# core09gnd.net
KiCad netlist of a schematic drawn in EAGLE
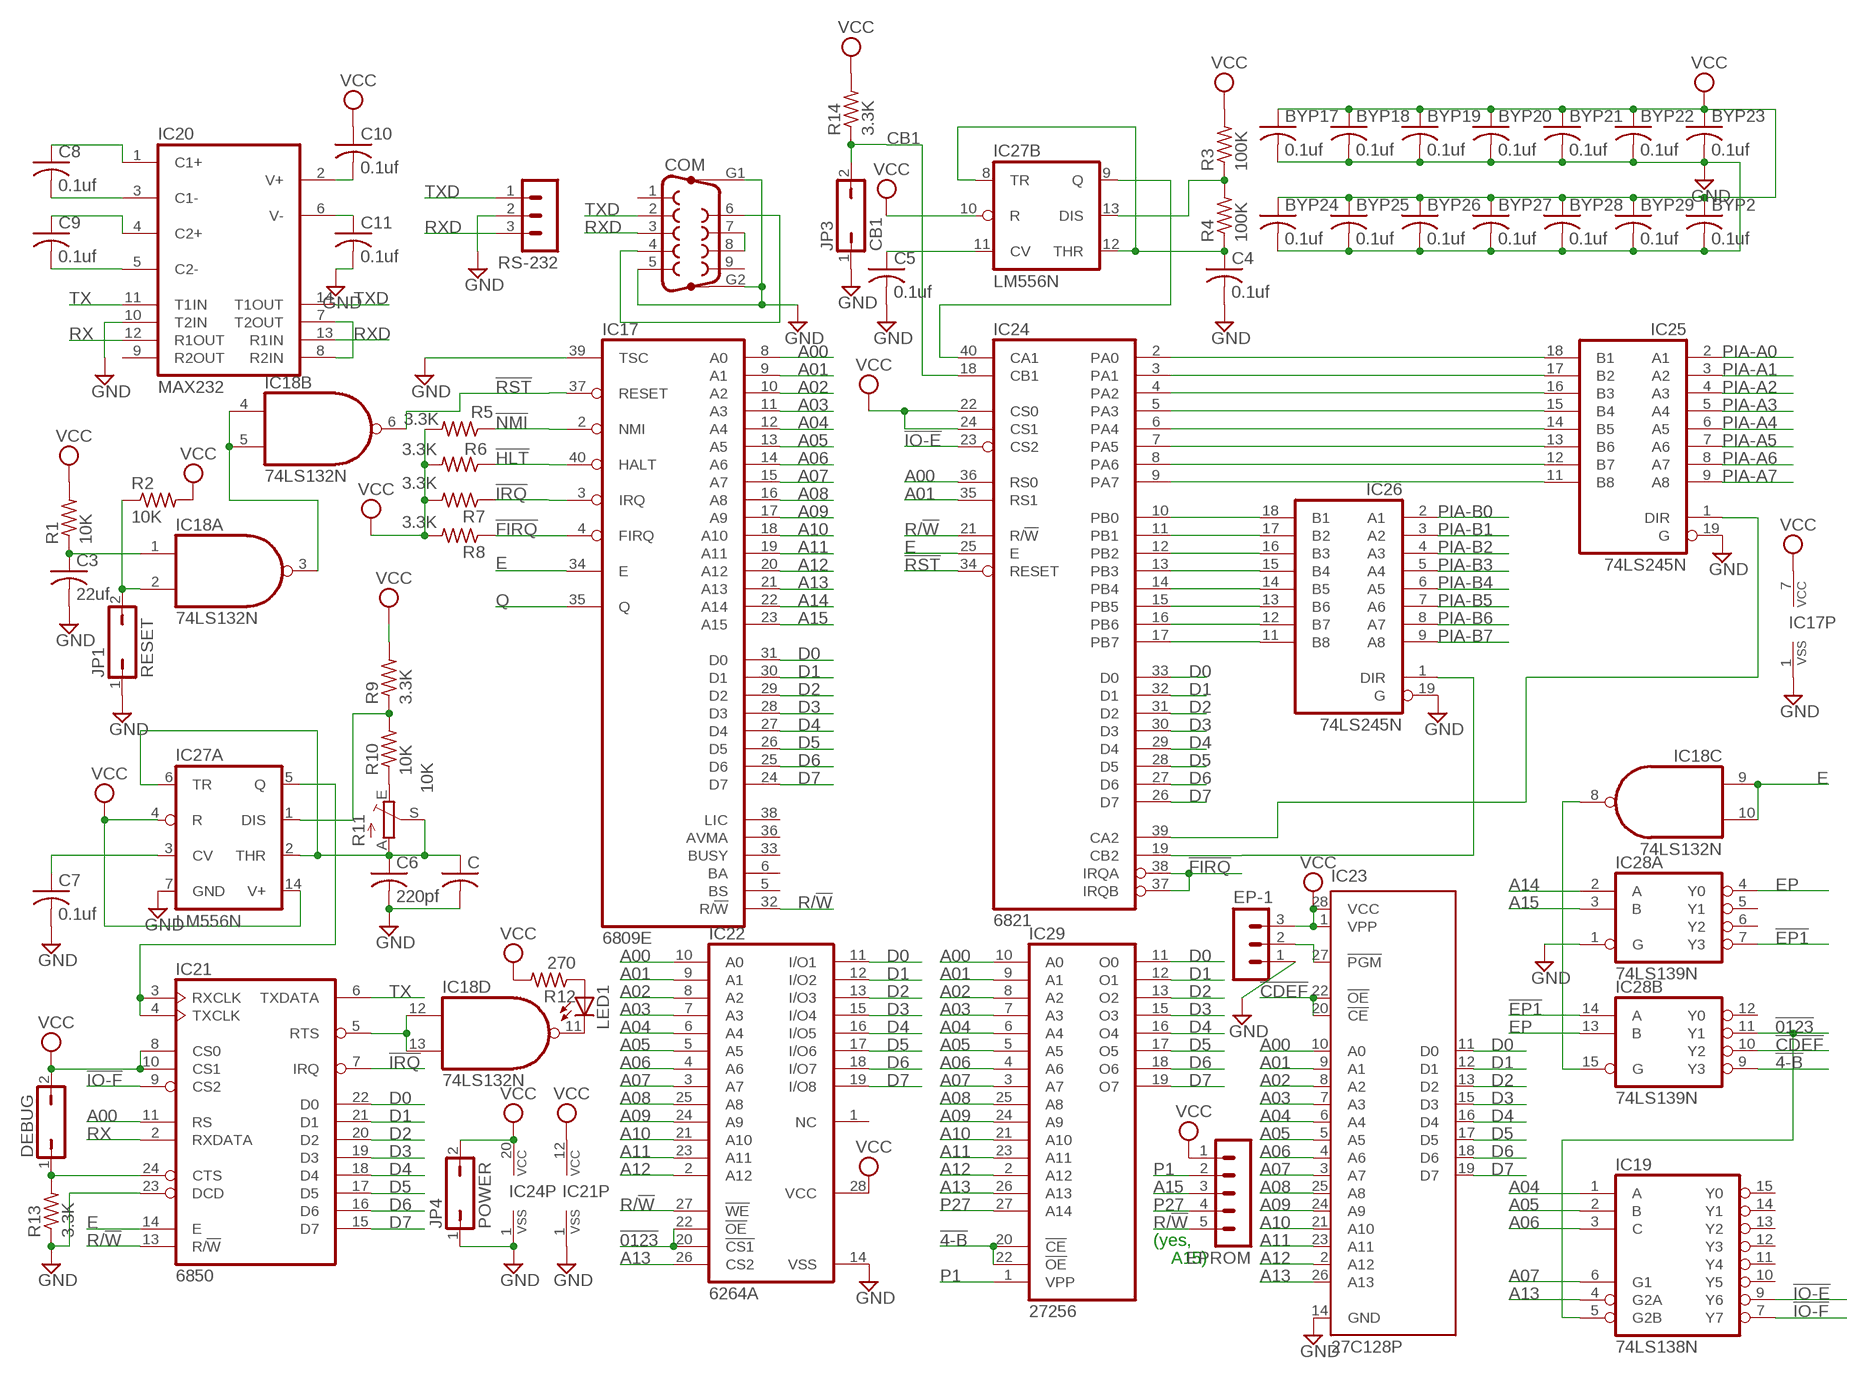
[diagram p0: schematic, sheet 1]
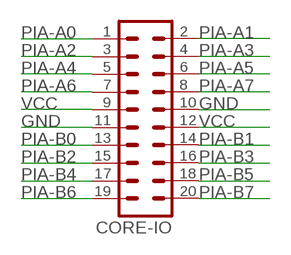
[diagram p1: schematic, sheet 2]
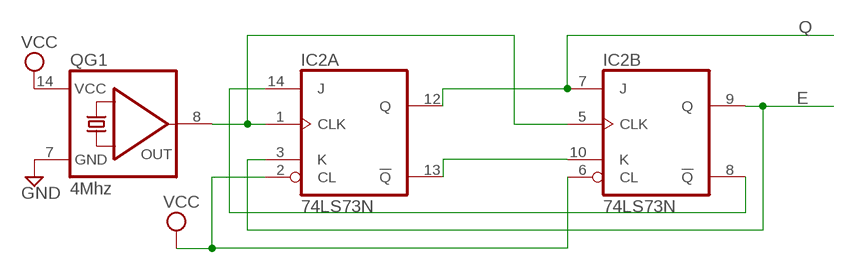
[diagram p2: schematic, sheet 3]

(export (version "E")
  (design (tool "Eeschema 10.0.6"))
  (components
    (comp (ref "IC2")
      (value "74LS73N")
      (footprint "eagle-import:DIL14")
      (libsource (lib "eagle-import") (part "7473NLS"))
    )
    (comp (ref "QG1")
      (value "4Mhz")
      (footprint "eagle-import:DIL14S")
      (libsource (lib "eagle-import") (part "QG5860"))
    )
    (comp (ref "BYP2")
      (value "0.1uf")
      (footprint "eagle-import:C050-025X075")
      (libsource (lib "eagle-import") (part "C-US050-025X075"))
    )
    (comp (ref "BYP17")
      (value "0.1uf")
      (footprint "eagle-import:C050-025X075")
      (libsource (lib "eagle-import") (part "C-US050-025X075"))
    )
    (comp (ref "BYP18")
      (value "0.1uf")
      (footprint "eagle-import:C050-025X075")
      (libsource (lib "eagle-import") (part "C-US050-025X075"))
    )
    (comp (ref "BYP19")
      (value "0.1uf")
      (footprint "eagle-import:C050-025X075")
      (libsource (lib "eagle-import") (part "C-US050-025X075"))
    )
    (comp (ref "BYP20")
      (value "0.1uf")
      (footprint "eagle-import:C050-025X075")
      (libsource (lib "eagle-import") (part "C-US050-025X075"))
    )
    (comp (ref "BYP21")
      (value "0.1uf")
      (footprint "eagle-import:C050-025X075")
      (libsource (lib "eagle-import") (part "C-US050-025X075"))
    )
    (comp (ref "BYP22")
      (value "0.1uf")
      (footprint "eagle-import:C050-025X075")
      (libsource (lib "eagle-import") (part "C-US050-025X075"))
    )
    (comp (ref "BYP23")
      (value "0.1uf")
      (footprint "eagle-import:C050-025X075")
      (libsource (lib "eagle-import") (part "C-US050-025X075"))
    )
    (comp (ref "BYP24")
      (value "0.1uf")
      (footprint "eagle-import:C050-025X075")
      (libsource (lib "eagle-import") (part "C-US050-025X075"))
    )
    (comp (ref "BYP25")
      (value "0.1uf")
      (footprint "eagle-import:C050-025X075")
      (libsource (lib "eagle-import") (part "C-US050-025X075"))
    )
    (comp (ref "BYP26")
      (value "0.1uf")
      (footprint "eagle-import:C050-025X075")
      (libsource (lib "eagle-import") (part "C-US050-025X075"))
    )
    (comp (ref "BYP27")
      (value "0.1uf")
      (footprint "eagle-import:C050-025X075")
      (libsource (lib "eagle-import") (part "C-US050-025X075"))
    )
    (comp (ref "BYP28")
      (value "0.1uf")
      (footprint "eagle-import:C050-025X075")
      (libsource (lib "eagle-import") (part "C-US050-025X075"))
    )
    (comp (ref "BYP29")
      (value "0.1uf")
      (footprint "eagle-import:C050-025X075")
      (libsource (lib "eagle-import") (part "C-US050-025X075"))
    )
    (comp (ref "C")
      (value "C-US050-025X075")
      (footprint "eagle-import:C050-025X075")
      (libsource (lib "eagle-import") (part "C-US050-025X075"))
    )
    (comp (ref "C3")
      (value "22uf")
      (footprint "eagle-import:C102-054X133")
      (libsource (lib "eagle-import") (part "C-US102-054X133"))
    )
    (comp (ref "C4")
      (value "0.1uf")
      (footprint "eagle-import:C050-025X075")
      (libsource (lib "eagle-import") (part "C-US050-025X075"))
    )
    (comp (ref "C5")
      (value "0.1uf")
      (footprint "eagle-import:C050-025X075")
      (libsource (lib "eagle-import") (part "C-US050-025X075"))
    )
    (comp (ref "C6")
      (value "220pf")
      (footprint "eagle-import:C050-025X075")
      (libsource (lib "eagle-import") (part "C-US050-025X075"))
    )
    (comp (ref "C7")
      (value "0.1uf")
      (footprint "eagle-import:C050-025X075")
      (libsource (lib "eagle-import") (part "C-US050-025X075"))
    )
    (comp (ref "C8")
      (value "0.1uf")
      (footprint "eagle-import:C050-025X075")
      (libsource (lib "eagle-import") (part "C-US050-025X075"))
    )
    (comp (ref "C9")
      (value "0.1uf")
      (footprint "eagle-import:C050-025X075")
      (libsource (lib "eagle-import") (part "C-US050-025X075"))
    )
    (comp (ref "C10")
      (value "0.1uf")
      (footprint "eagle-import:C050-025X075")
      (libsource (lib "eagle-import") (part "C-US050-025X075"))
    )
    (comp (ref "C11")
      (value "0.1uf")
      (footprint "eagle-import:C050-025X075")
      (libsource (lib "eagle-import") (part "C-US050-025X075"))
    )
    (comp (ref "COM")
      (value "F09HP")
      (footprint "eagle-import:F09HP")
      (libsource (lib "eagle-import") (part "F09HP"))
    )
    (comp (ref "DEBUG")
      (value "JP1Q")
      (footprint "eagle-import:JP1")
      (libsource (lib "eagle-import") (part "JP1Q"))
    )
    (comp (ref "EP-1")
      (value "MA03-1")
      (footprint "eagle-import:MA03-1")
      (libsource (lib "eagle-import") (part "MA03-1"))
    )
    (comp (ref "EPROM")
      (value "MA05-1")
      (footprint "eagle-import:MA05-1")
      (libsource (lib "eagle-import") (part "MA05-1"))
    )
    (comp (ref "IC17")
      (value "6809E")
      (footprint "eagle-import:DIL40")
      (fields (field (name "MF") "NTE ELECTRONICS") (field (name "MPN") "NTE6809E"))
      (libsource (lib "eagle-import") (part "6809E"))
    )
    (comp (ref "IC18")
      (value "74LS132N")
      (footprint "eagle-import:DIL14")
      (libsource (lib "eagle-import") (part "7400NLS"))
    )
    (comp (ref "IC19")
      (value "74LS138N")
      (footprint "eagle-import:DIL16")
      (libsource (lib "eagle-import") (part "74138NLS"))
    )
    (comp (ref "IC20")
      (value "MAX232")
      (footprint "eagle-import:DIL16")
      (fields (field (name "MF") "MAXIM") (field (name "MPN") "MAX232ACPE+"))
      (libsource (lib "eagle-import") (part "MAX232"))
    )
    (comp (ref "IC21")
      (value "6850")
      (footprint "eagle-import:DIL24")
      (fields (field (name "MF") "NTE ELECTRONICS") (field (name "MPN") "NTE6850"))
      (libsource (lib "eagle-import") (part "6850"))
    )
    (comp (ref "IC22")
      (value "6264A")
      (footprint "eagle-import:DIL28-6")
      (libsource (lib "eagle-import") (part "6264A"))
    )
    (comp (ref "IC23")
      (value "27C128P")
      (footprint "eagle-import:DIL28-6")
      (libsource (lib "eagle-import") (part "27128PC"))
    )
    (comp (ref "IC24")
      (value "6821")
      (footprint "eagle-import:DIL40")
      (fields (field (name "MF") "NTE ELECTRONICS") (field (name "MPN") "NTE6821"))
      (libsource (lib "eagle-import") (part "6821"))
    )
    (comp (ref "IC25")
      (value "74LS245N")
      (footprint "eagle-import:DIL20")
      (libsource (lib "eagle-import") (part "74245NLS"))
    )
    (comp (ref "IC26")
      (value "74LS245N")
      (footprint "eagle-import:DIL20")
      (libsource (lib "eagle-import") (part "74245NLS"))
    )
    (comp (ref "IC27")
      (value "LM556N")
      (footprint "eagle-import:DIL14")
      (libsource (lib "eagle-import") (part "556NLM"))
    )
    (comp (ref "IC28")
      (value "74LS139N")
      (footprint "eagle-import:DIL16")
      (libsource (lib "eagle-import") (part "74139NLS"))
    )
    (comp (ref "IC29")
      (value "27256")
      (footprint "eagle-import:DIL28")
      (libsource (lib "eagle-import") (part "27256"))
    )
    (comp (ref "JP1")
      (value "RESET")
      (footprint "eagle-import:JP1")
      (libsource (lib "eagle-import") (part "JP1Q"))
    )
    (comp (ref "JP3")
      (value "CB1")
      (footprint "eagle-import:JP1")
      (libsource (lib "eagle-import") (part "JP1Q"))
    )
    (comp (ref "JP4")
      (value "POWER")
      (footprint "eagle-import:JP1")
      (libsource (lib "eagle-import") (part "JP1Q"))
    )
    (comp (ref "LED1")
      (value "LED3MM")
      (footprint "eagle-import:LED3MM")
      (libsource (lib "eagle-import") (part "LED3MM"))
    )
    (comp (ref "R1")
      (value "10K")
      (footprint "eagle-import:0207_7")
      (libsource (lib "eagle-import") (part "R-US_0207/7"))
    )
    (comp (ref "R2")
      (value "10K")
      (footprint "eagle-import:0207_7")
      (libsource (lib "eagle-import") (part "R-US_0207/7"))
    )
    (comp (ref "R3")
      (value "100K")
      (footprint "eagle-import:0207_7")
      (libsource (lib "eagle-import") (part "R-US_0207/7"))
    )
    (comp (ref "R4")
      (value "100K")
      (footprint "eagle-import:0207_7")
      (libsource (lib "eagle-import") (part "R-US_0207/7"))
    )
    (comp (ref "R5")
      (value "3.3K")
      (footprint "eagle-import:0207_7")
      (libsource (lib "eagle-import") (part "R-US_0207/7"))
    )
    (comp (ref "R6")
      (value "3.3K")
      (footprint "eagle-import:0207_7")
      (libsource (lib "eagle-import") (part "R-US_0207/7"))
    )
    (comp (ref "R7")
      (value "3.3K")
      (footprint "eagle-import:0207_7")
      (libsource (lib "eagle-import") (part "R-US_0207/7"))
    )
    (comp (ref "R8")
      (value "3.3K")
      (footprint "eagle-import:0207_7")
      (libsource (lib "eagle-import") (part "R-US_0207/7"))
    )
    (comp (ref "R9")
      (value "3.3K")
      (footprint "eagle-import:0207_7")
      (libsource (lib "eagle-import") (part "R-US_0207/7"))
    )
    (comp (ref "R10")
      (value "10K")
      (footprint "eagle-import:0207_7")
      (libsource (lib "eagle-import") (part "R-US_0207/7"))
    )
    (comp (ref "R11")
      (value "10K")
      (footprint "eagle-import:SP19L")
      (libsource (lib "eagle-import") (part "TRIM_EU-B90P"))
    )
    (comp (ref "R12")
      (value "270")
      (footprint "eagle-import:0207_7")
      (libsource (lib "eagle-import") (part "R-US_0207/7"))
    )
    (comp (ref "R13")
      (value "3.3K")
      (footprint "eagle-import:0207_7")
      (libsource (lib "eagle-import") (part "R-US_0207/7"))
    )
    (comp (ref "R14")
      (value "3.3K")
      (footprint "eagle-import:0207_7")
      (libsource (lib "eagle-import") (part "R-US_0207/7"))
    )
    (comp (ref "RS-232")
      (value "MA03-1")
      (footprint "eagle-import:MA03-1")
      (libsource (lib "eagle-import") (part "MA03-1"))
    )
    (comp (ref "CORE-IO")
      (value "MA10-2")
      (footprint "eagle-import:MA10-2")
      (libsource (lib "eagle-import") (part "MA10-2"))
    )
  )
  (nets
    (net (code "1") (name "A00") (class "Default")
      (node (ref "IC17") (pin "8") (pinfunction "A0_8") (pintype "tri_state"))
      (node (ref "IC21") (pin "11") (pinfunction "RS_11") (pintype "input"))
      (node (ref "IC22") (pin "10") (pinfunction "A0_10") (pintype "input"))
      (node (ref "IC23") (pin "10") (pinfunction "A0_10") (pintype "input"))
      (node (ref "IC24") (pin "36") (pinfunction "RS0_36") (pintype "input"))
      (node (ref "IC29") (pin "10") (pinfunction "A0_10") (pintype "input"))
    )
    (net (code "2") (name "A01") (class "Default")
      (node (ref "IC17") (pin "9") (pinfunction "A1_9") (pintype "tri_state"))
      (node (ref "IC22") (pin "9") (pinfunction "A1_9") (pintype "input"))
      (node (ref "IC23") (pin "9") (pinfunction "A1_9") (pintype "input"))
      (node (ref "IC24") (pin "35") (pinfunction "RS1_35") (pintype "input"))
      (node (ref "IC29") (pin "9") (pinfunction "A1_9") (pintype "input"))
    )
    (net (code "3") (name "A02") (class "Default")
      (node (ref "IC17") (pin "10") (pinfunction "A2_10") (pintype "tri_state"))
      (node (ref "IC22") (pin "8") (pinfunction "A2_8") (pintype "input"))
      (node (ref "IC23") (pin "8") (pinfunction "A2_8") (pintype "input"))
      (node (ref "IC29") (pin "8") (pinfunction "A2_8") (pintype "input"))
    )
    (net (code "4") (name "A03") (class "Default")
      (node (ref "IC17") (pin "11") (pinfunction "A3_11") (pintype "tri_state"))
      (node (ref "IC22") (pin "7") (pinfunction "A3_7") (pintype "input"))
      (node (ref "IC23") (pin "7") (pinfunction "A3_7") (pintype "input"))
      (node (ref "IC29") (pin "7") (pinfunction "A3_7") (pintype "input"))
    )
    (net (code "5") (name "A04") (class "Default")
      (node (ref "IC17") (pin "12") (pinfunction "A4_12") (pintype "tri_state"))
      (node (ref "IC19") (pin "1") (pinfunction "A_1") (pintype "input"))
      (node (ref "IC22") (pin "6") (pinfunction "A4_6") (pintype "input"))
      (node (ref "IC23") (pin "6") (pinfunction "A4_6") (pintype "input"))
      (node (ref "IC29") (pin "6") (pinfunction "A4_6") (pintype "input"))
    )
    (net (code "6") (name "A05") (class "Default")
      (node (ref "IC17") (pin "13") (pinfunction "A5_13") (pintype "tri_state"))
      (node (ref "IC19") (pin "2") (pinfunction "B_2") (pintype "input"))
      (node (ref "IC22") (pin "5") (pinfunction "A5_5") (pintype "input"))
      (node (ref "IC23") (pin "5") (pinfunction "A5_5") (pintype "input"))
      (node (ref "IC29") (pin "5") (pinfunction "A5_5") (pintype "input"))
    )
    (net (code "7") (name "A06") (class "Default")
      (node (ref "IC17") (pin "14") (pinfunction "A6_14") (pintype "tri_state"))
      (node (ref "IC19") (pin "3") (pinfunction "C_3") (pintype "input"))
      (node (ref "IC22") (pin "4") (pinfunction "A6_4") (pintype "input"))
      (node (ref "IC23") (pin "4") (pinfunction "A6_4") (pintype "input"))
      (node (ref "IC29") (pin "4") (pinfunction "A6_4") (pintype "input"))
    )
    (net (code "8") (name "A07") (class "Default")
      (node (ref "IC17") (pin "15") (pinfunction "A7_15") (pintype "tri_state"))
      (node (ref "IC19") (pin "6") (pinfunction "G1_6") (pintype "input"))
      (node (ref "IC22") (pin "3") (pinfunction "A7_3") (pintype "input"))
      (node (ref "IC23") (pin "3") (pinfunction "A7_3") (pintype "input"))
      (node (ref "IC29") (pin "3") (pinfunction "A7_3") (pintype "input"))
    )
    (net (code "9") (name "A08") (class "Default")
      (node (ref "IC17") (pin "16") (pinfunction "A8_16") (pintype "tri_state"))
      (node (ref "IC22") (pin "25") (pinfunction "A8_25") (pintype "input"))
      (node (ref "IC23") (pin "25") (pinfunction "A8_25") (pintype "input"))
      (node (ref "IC29") (pin "25") (pinfunction "A8_25") (pintype "input"))
    )
    (net (code "10") (name "A09") (class "Default")
      (node (ref "IC17") (pin "17") (pinfunction "A9_17") (pintype "tri_state"))
      (node (ref "IC22") (pin "24") (pinfunction "A9_24") (pintype "input"))
      (node (ref "IC23") (pin "24") (pinfunction "A9_24") (pintype "input"))
      (node (ref "IC29") (pin "24") (pinfunction "A9_24") (pintype "input"))
    )
    (net (code "11") (name "A10") (class "Default")
      (node (ref "IC17") (pin "18") (pinfunction "A10_18") (pintype "tri_state"))
      (node (ref "IC22") (pin "21") (pinfunction "A10_21") (pintype "input"))
      (node (ref "IC23") (pin "21") (pinfunction "A10_21") (pintype "input"))
      (node (ref "IC29") (pin "21") (pinfunction "A10_21") (pintype "input"))
    )
    (net (code "12") (name "A11") (class "Default")
      (node (ref "IC17") (pin "19") (pinfunction "A11_19") (pintype "tri_state"))
      (node (ref "IC22") (pin "23") (pinfunction "A11_23") (pintype "input"))
      (node (ref "IC23") (pin "23") (pinfunction "A11_23") (pintype "input"))
      (node (ref "IC29") (pin "23") (pinfunction "A11_23") (pintype "input"))
    )
    (net (code "13") (name "A12") (class "Default")
      (node (ref "IC17") (pin "20") (pinfunction "A12_20") (pintype "tri_state"))
      (node (ref "IC22") (pin "2") (pinfunction "A12_2") (pintype "input"))
      (node (ref "IC23") (pin "2") (pinfunction "A12_2") (pintype "input"))
      (node (ref "IC29") (pin "2") (pinfunction "A12_2") (pintype "input"))
    )
    (net (code "14") (name "A13") (class "Default")
      (node (ref "IC17") (pin "21") (pinfunction "A13_21") (pintype "tri_state"))
      (node (ref "IC19") (pin "4") (pinfunction "G2A_4") (pintype "input"))
      (node (ref "IC22") (pin "26") (pinfunction "CS2_26") (pintype "input"))
      (node (ref "IC23") (pin "26") (pinfunction "A13_26") (pintype "input"))
      (node (ref "IC29") (pin "26") (pinfunction "A13_26") (pintype "input"))
    )
    (net (code "15") (name "A14") (class "Default")
      (node (ref "IC17") (pin "22") (pinfunction "A14_22") (pintype "tri_state"))
      (node (ref "IC28") (pin "2") (pinfunction "A_2") (pintype "input"))
    )
    (net (code "16") (name "A15") (class "Default")
      (node (ref "EPROM") (pin "3") (pinfunction "3_3") (pintype "passive"))
      (node (ref "IC17") (pin "23") (pinfunction "A15_23") (pintype "tri_state"))
      (node (ref "IC28") (pin "3") (pinfunction "B_3") (pintype "input"))
    )
    (net (code "17") (name "CB1") (class "Default")
      (node (ref "IC24") (pin "18") (pinfunction "CB1_18") (pintype "input"))
      (node (ref "JP3") (pin "2") (pinfunction "2_2") (pintype "passive"))
      (node (ref "R14") (pin "1") (pinfunction "1_1") (pintype "passive"))
    )
    (net (code "18") (name "D0") (class "Default")
      (node (ref "IC17") (pin "31") (pinfunction "D0_31") (pintype "bidirectional"))
      (node (ref "IC21") (pin "22") (pinfunction "D0_22") (pintype "bidirectional"))
      (node (ref "IC22") (pin "11") (pinfunction "I/O1_11") (pintype "bidirectional"))
      (node (ref "IC23") (pin "11") (pinfunction "D0_11") (pintype "tri_state"))
      (node (ref "IC24") (pin "33") (pinfunction "D0_33") (pintype "bidirectional"))
      (node (ref "IC29") (pin "11") (pinfunction "O0_11") (pintype "tri_state"))
    )
    (net (code "19") (name "D1") (class "Default")
      (node (ref "IC17") (pin "30") (pinfunction "D1_30") (pintype "bidirectional"))
      (node (ref "IC21") (pin "21") (pinfunction "D1_21") (pintype "bidirectional"))
      (node (ref "IC22") (pin "12") (pinfunction "I/O2_12") (pintype "bidirectional"))
      (node (ref "IC23") (pin "12") (pinfunction "D1_12") (pintype "tri_state"))
      (node (ref "IC24") (pin "32") (pinfunction "D1_32") (pintype "bidirectional"))
      (node (ref "IC29") (pin "12") (pinfunction "O1_12") (pintype "tri_state"))
    )
    (net (code "20") (name "D2") (class "Default")
      (node (ref "IC17") (pin "29") (pinfunction "D2_29") (pintype "bidirectional"))
      (node (ref "IC21") (pin "20") (pinfunction "D2_20") (pintype "bidirectional"))
      (node (ref "IC22") (pin "13") (pinfunction "I/O3_13") (pintype "bidirectional"))
      (node (ref "IC23") (pin "13") (pinfunction "D2_13") (pintype "tri_state"))
      (node (ref "IC24") (pin "31") (pinfunction "D2_31") (pintype "bidirectional"))
      (node (ref "IC29") (pin "13") (pinfunction "O2_13") (pintype "tri_state"))
    )
    (net (code "21") (name "D3") (class "Default")
      (node (ref "IC17") (pin "28") (pinfunction "D3_28") (pintype "bidirectional"))
      (node (ref "IC21") (pin "19") (pinfunction "D3_19") (pintype "bidirectional"))
      (node (ref "IC22") (pin "15") (pinfunction "I/O4_15") (pintype "bidirectional"))
      (node (ref "IC23") (pin "15") (pinfunction "D3_15") (pintype "tri_state"))
      (node (ref "IC24") (pin "30") (pinfunction "D3_30") (pintype "bidirectional"))
      (node (ref "IC29") (pin "15") (pinfunction "O3_15") (pintype "tri_state"))
    )
    (net (code "22") (name "D4") (class "Default")
      (node (ref "IC17") (pin "27") (pinfunction "D4_27") (pintype "bidirectional"))
      (node (ref "IC21") (pin "18") (pinfunction "D4_18") (pintype "bidirectional"))
      (node (ref "IC22") (pin "16") (pinfunction "I/O5_16") (pintype "bidirectional"))
      (node (ref "IC23") (pin "16") (pinfunction "D4_16") (pintype "tri_state"))
      (node (ref "IC24") (pin "29") (pinfunction "D4_29") (pintype "bidirectional"))
      (node (ref "IC29") (pin "16") (pinfunction "O4_16") (pintype "tri_state"))
    )
    (net (code "23") (name "D5") (class "Default")
      (node (ref "IC17") (pin "26") (pinfunction "D5_26") (pintype "bidirectional"))
      (node (ref "IC21") (pin "17") (pinfunction "D5_17") (pintype "bidirectional"))
      (node (ref "IC22") (pin "17") (pinfunction "I/O6_17") (pintype "bidirectional"))
      (node (ref "IC23") (pin "17") (pinfunction "D5_17") (pintype "tri_state"))
      (node (ref "IC24") (pin "28") (pinfunction "D5_28") (pintype "bidirectional"))
      (node (ref "IC29") (pin "17") (pinfunction "O5_17") (pintype "tri_state"))
    )
    (net (code "24") (name "D6") (class "Default")
      (node (ref "IC17") (pin "25") (pinfunction "D6_25") (pintype "bidirectional"))
      (node (ref "IC21") (pin "16") (pinfunction "D6_16") (pintype "bidirectional"))
      (node (ref "IC22") (pin "18") (pinfunction "I/O7_18") (pintype "bidirectional"))
      (node (ref "IC23") (pin "18") (pinfunction "D6_18") (pintype "tri_state"))
      (node (ref "IC24") (pin "27") (pinfunction "D6_27") (pintype "bidirectional"))
      (node (ref "IC29") (pin "18") (pinfunction "O6_18") (pintype "tri_state"))
    )
    (net (code "25") (name "D7") (class "Default")
      (node (ref "IC17") (pin "24") (pinfunction "D7_24") (pintype "bidirectional"))
      (node (ref "IC21") (pin "15") (pinfunction "D7_15") (pintype "bidirectional"))
      (node (ref "IC22") (pin "19") (pinfunction "I/O8_19") (pintype "bidirectional"))
      (node (ref "IC23") (pin "19") (pinfunction "D7_19") (pintype "tri_state"))
      (node (ref "IC24") (pin "26") (pinfunction "D7_26") (pintype "bidirectional"))
      (node (ref "IC29") (pin "19") (pinfunction "O7_19") (pintype "tri_state"))
    )
    (net (code "26") (name "E") (class "Default")
      (node (ref "IC17") (pin "34") (pinfunction "E_34") (pintype "input"))
      (node (ref "IC18") (pin "10") (pinfunction "I1_10") (pintype "input"))
      (node (ref "IC18") (pin "9") (pinfunction "I0_9") (pintype "input"))
      (node (ref "IC2") (pin "3") (pinfunction "K_3") (pintype "input"))
      (node (ref "IC2") (pin "9") (pinfunction "Q_9") (pintype "output"))
      (node (ref "IC21") (pin "14") (pinfunction "E_14") (pintype "input"))
      (node (ref "IC24") (pin "25") (pinfunction "E_25") (pintype "input"))
    )
    (net (code "27") (name "EP") (class "Default")
      (node (ref "IC28") (pin "13") (pinfunction "B_13") (pintype "input"))
      (node (ref "IC28") (pin "4") (pinfunction "Y0_4") (pintype "output"))
    )
    (net (code "28") (name "GND") (class "Default")
      (node (ref "BYP17") (pin "2") (pinfunction "2_2") (pintype "passive"))
      (node (ref "BYP18") (pin "2") (pinfunction "2_2") (pintype "passive"))
      (node (ref "BYP19") (pin "2") (pinfunction "2_2") (pintype "passive"))
      (node (ref "BYP2") (pin "2") (pinfunction "2_2") (pintype "passive"))
      (node (ref "BYP20") (pin "2") (pinfunction "2_2") (pintype "passive"))
      (node (ref "BYP21") (pin "2") (pinfunction "2_2") (pintype "passive"))
      (node (ref "BYP22") (pin "2") (pinfunction "2_2") (pintype "passive"))
      (node (ref "BYP23") (pin "2") (pinfunction "2_2") (pintype "passive"))
      (node (ref "BYP24") (pin "2") (pinfunction "2_2") (pintype "passive"))
      (node (ref "BYP25") (pin "2") (pinfunction "2_2") (pintype "passive"))
      (node (ref "BYP26") (pin "2") (pinfunction "2_2") (pintype "passive"))
      (node (ref "BYP27") (pin "2") (pinfunction "2_2") (pintype "passive"))
      (node (ref "BYP28") (pin "2") (pinfunction "2_2") (pintype "passive"))
      (node (ref "BYP29") (pin "2") (pinfunction "2_2") (pintype "passive"))
      (node (ref "C") (pin "2") (pinfunction "2_2") (pintype "passive"))
      (node (ref "C11") (pin "2") (pinfunction "2_2") (pintype "passive"))
      (node (ref "C3") (pin "2") (pinfunction "2_2") (pintype "passive"))
      (node (ref "C4") (pin "2") (pinfunction "2_2") (pintype "passive"))
      (node (ref "C5") (pin "2") (pinfunction "2_2") (pintype "passive"))
      (node (ref "C6") (pin "2") (pinfunction "2_2") (pintype "passive"))
      (node (ref "C7") (pin "2") (pinfunction "2_2") (pintype "passive"))
      (node (ref "COM") (pin "5") (pinfunction "5_5") (pintype "passive"))
      (node (ref "COM") (pin "G1") (pinfunction "G1_G1") (pintype "passive"))
      (node (ref "COM") (pin "G2") (pinfunction "G2_G2") (pintype "passive"))
      (node (ref "CORE-IO") (pin "10") (pinfunction "10_10") (pintype "passive"))
      (node (ref "CORE-IO") (pin "11") (pinfunction "11_11") (pintype "passive"))
      (node (ref "EP-1") (pin "1") (pinfunction "1_1") (pintype "passive"))
      (node (ref "IC17") (pin "1") (pinfunction "VSS_1") (pintype "power_in"))
      (node (ref "IC17") (pin "39") (pinfunction "TSC_39") (pintype "input"))
      (node (ref "IC20") (pin "10") (pinfunction "T2IN_10") (pintype "input"))
      (node (ref "IC21") (pin "1") (pinfunction "VSS_1") (pintype "power_in"))
      (node (ref "IC21") (pin "23") (pinfunction "DCD_23") (pintype "input"))
      (node (ref "IC22") (pin "14") (pinfunction "VSS_14") (pintype "power_in"))
      (node (ref "IC23") (pin "14") (pinfunction "GND_14") (pintype "power_in"))
      (node (ref "IC24") (pin "1") (pinfunction "VSS_1") (pintype "power_in"))
      (node (ref "IC25") (pin "19") (pinfunction "G_19") (pintype "input"))
      (node (ref "IC26") (pin "19") (pinfunction "G_19") (pintype "input"))
      (node (ref "IC27") (pin "7") (pinfunction "GND_7") (pintype "power_in"))
      (node (ref "IC28") (pin "1") (pinfunction "G_1") (pintype "input"))
      (node (ref "JP1") (pin "1") (pinfunction "1_1") (pintype "passive"))
      (node (ref "JP3") (pin "1") (pinfunction "1_1") (pintype "passive"))
      (node (ref "JP4") (pin "1") (pinfunction "1_1") (pintype "passive"))
      (node (ref "QG1") (pin "7") (pinfunction "GND_7") (pintype "power_in"))
      (node (ref "R13") (pin "1") (pinfunction "1_1") (pintype "passive"))
      (node (ref "RS-232") (pin "2") (pinfunction "2_2") (pintype "passive"))
    )
    (net (code "29") (name "Net-(COM-Pad4)") (class "Default")
      (node (ref "COM") (pin "4") (pinfunction "4_4") (pintype "passive"))
      (node (ref "COM") (pin "6") (pinfunction "6_6") (pintype "passive"))
    )
    (net (code "30") (name "Net-(COM-Pad7)") (class "Default")
      (node (ref "COM") (pin "7") (pinfunction "7_7") (pintype "passive"))
      (node (ref "COM") (pin "8") (pinfunction "8_8") (pintype "passive"))
    )
    (net (code "31") (name "Net-(IC2A-CLK)") (class "Default")
      (node (ref "IC2") (pin "1") (pinfunction "CLK_1") (pintype "input"))
      (node (ref "IC2") (pin "5") (pinfunction "CLK_5") (pintype "input"))
      (node (ref "QG1") (pin "8") (pinfunction "OUT_8") (pintype "output"))
    )
    (net (code "32") (name "Net-(IC2A-J)") (class "Default")
      (node (ref "IC2") (pin "14") (pinfunction "J_14") (pintype "input"))
      (node (ref "IC2") (pin "8") (pinfunction "~{Q}_8") (pintype "output"))
    )
    (net (code "33") (name "Net-(IC2A-~{Q})") (class "Default")
      (node (ref "IC2") (pin "10") (pinfunction "K_10") (pintype "input"))
      (node (ref "IC2") (pin "13") (pinfunction "~{Q}_13") (pintype "output"))
    )
    (net (code "34") (name "Net-(IC18A-I0)") (class "Default")
      (node (ref "C3") (pin "1") (pinfunction "1_1") (pintype "passive"))
      (node (ref "IC18") (pin "1") (pinfunction "I0_1") (pintype "input"))
      (node (ref "R1") (pin "1") (pinfunction "1_1") (pintype "passive"))
    )
    (net (code "35") (name "Net-(IC18A-I1)") (class "Default")
      (node (ref "IC18") (pin "2") (pinfunction "I1_2") (pintype "input"))
      (node (ref "JP1") (pin "2") (pinfunction "2_2") (pintype "passive"))
      (node (ref "R2") (pin "1") (pinfunction "1_1") (pintype "passive"))
    )
    (net (code "36") (name "Net-(IC18A-O)") (class "Default")
      (node (ref "IC18") (pin "3") (pinfunction "O_3") (pintype "output"))
      (node (ref "IC18") (pin "4") (pinfunction "I0_4") (pintype "input"))
      (node (ref "IC18") (pin "5") (pinfunction "I1_5") (pintype "input"))
    )
    (net (code "37") (name "Net-(IC18C-O)") (class "Default")
      (node (ref "IC18") (pin "8") (pinfunction "O_8") (pintype "output"))
      (node (ref "IC28") (pin "15") (pinfunction "G_15") (pintype "input"))
    )
    (net (code "38") (name "Net-(IC18D-I0)") (class "Default")
      (node (ref "IC18") (pin "12") (pinfunction "I0_12") (pintype "input"))
      (node (ref "IC18") (pin "13") (pinfunction "I1_13") (pintype "input"))
      (node (ref "IC21") (pin "5") (pinfunction "RTS_5") (pintype "output"))
    )
    (net (code "39") (name "Net-(IC18D-O)") (class "Default")
      (node (ref "IC18") (pin "11") (pinfunction "O_11") (pintype "output"))
      (node (ref "LED1") (pin "K") (pinfunction "C_K") (pintype "passive"))
    )
    (net (code "40") (name "Net-(IC20A-C1+)") (class "Default")
      (node (ref "C8") (pin "1") (pinfunction "1_1") (pintype "passive"))
      (node (ref "IC20") (pin "1") (pinfunction "C1+_1") (pintype "bidirectional"))
    )
    (net (code "41") (name "Net-(IC20A-C1-)") (class "Default")
      (node (ref "C8") (pin "2") (pinfunction "2_2") (pintype "passive"))
      (node (ref "IC20") (pin "3") (pinfunction "C1-_3") (pintype "bidirectional"))
    )
    (net (code "42") (name "Net-(IC20A-C2+)") (class "Default")
      (node (ref "C9") (pin "1") (pinfunction "1_1") (pintype "passive"))
      (node (ref "IC20") (pin "4") (pinfunction "C2+_4") (pintype "bidirectional"))
    )
    (net (code "43") (name "Net-(IC20A-C2-)") (class "Default")
      (node (ref "C9") (pin "2") (pinfunction "2_2") (pintype "passive"))
      (node (ref "IC20") (pin "5") (pinfunction "C2-_5") (pintype "bidirectional"))
    )
    (net (code "44") (name "Net-(IC20A-R2IN)") (class "Default")
      (node (ref "IC20") (pin "7") (pinfunction "T2OUT_7") (pintype "output"))
      (node (ref "IC20") (pin "8") (pinfunction "R2IN_8") (pintype "input"))
    )
    (net (code "45") (name "Net-(IC20A-V+)") (class "Default")
      (node (ref "C10") (pin "2") (pinfunction "2_2") (pintype "passive"))
      (node (ref "IC20") (pin "2") (pinfunction "V+_2") (pintype "bidirectional"))
    )
    (net (code "46") (name "Net-(IC20A-V-)") (class "Default")
      (node (ref "C11") (pin "1") (pinfunction "1_1") (pintype "passive"))
      (node (ref "IC20") (pin "6") (pinfunction "V-_6") (pintype "bidirectional"))
    )
    (net (code "47") (name "Net-(IC21A-CTS)") (class "Default")
      (node (ref "DEBUG") (pin "1") (pinfunction "1_1") (pintype "passive"))
      (node (ref "IC21") (pin "24") (pinfunction "CTS_24") (pintype "input"))
      (node (ref "R13") (pin "2") (pinfunction "2_2") (pintype "passive"))
    )
    (net (code "48") (name "Net-(IC21A-RXCLK)") (class "Default")
      (node (ref "IC21") (pin "3") (pinfunction "RXCLK_3") (pintype "input"))
      (node (ref "IC21") (pin "4") (pinfunction "TXCLK_4") (pintype "input"))
      (node (ref "IC27") (pin "5") (pinfunction "Q_5") (pintype "output"))
    )
    (net (code "49") (name "Net-(IC23-~{PGM})") (class "Default")
      (node (ref "EP-1") (pin "2") (pinfunction "2_2") (pintype "passive"))
      (node (ref "IC23") (pin "27") (pinfunction "~{PGM}_27") (pintype "passive"))
    )
    (net (code "50") (name "Net-(IC24A-CA1)") (class "Default")
      (node (ref "IC24") (pin "40") (pinfunction "CA1_40") (pintype "input"))
      (node (ref "IC27") (pin "9") (pinfunction "Q_9") (pintype "output"))
    )
    (net (code "51") (name "Net-(IC24A-CA2)") (class "Default")
      (node (ref "IC24") (pin "39") (pinfunction "CA2_39") (pintype "bidirectional"))
      (node (ref "IC25") (pin "1") (pinfunction "DIR_1") (pintype "input"))
    )
    (net (code "52") (name "Net-(IC24A-CB2)") (class "Default")
      (node (ref "IC24") (pin "19") (pinfunction "CB2_19") (pintype "bidirectional"))
      (node (ref "IC26") (pin "1") (pinfunction "DIR_1") (pintype "input"))
    )
    (net (code "53") (name "Net-(IC24A-PA0)") (class "Default")
      (node (ref "IC24") (pin "2") (pinfunction "PA0_2") (pintype "bidirectional"))
      (node (ref "IC25") (pin "18") (pinfunction "B1_18") (pintype "bidirectional"))
    )
    (net (code "54") (name "Net-(IC24A-PA1)") (class "Default")
      (node (ref "IC24") (pin "3") (pinfunction "PA1_3") (pintype "bidirectional"))
      (node (ref "IC25") (pin "17") (pinfunction "B2_17") (pintype "bidirectional"))
    )
    (net (code "55") (name "Net-(IC24A-PA2)") (class "Default")
      (node (ref "IC24") (pin "4") (pinfunction "PA2_4") (pintype "bidirectional"))
      (node (ref "IC25") (pin "16") (pinfunction "B3_16") (pintype "bidirectional"))
    )
    (net (code "56") (name "Net-(IC24A-PA3)") (class "Default")
      (node (ref "IC24") (pin "5") (pinfunction "PA3_5") (pintype "bidirectional"))
      (node (ref "IC25") (pin "15") (pinfunction "B4_15") (pintype "bidirectional"))
    )
    (net (code "57") (name "Net-(IC24A-PA4)") (class "Default")
      (node (ref "IC24") (pin "6") (pinfunction "PA4_6") (pintype "bidirectional"))
      (node (ref "IC25") (pin "14") (pinfunction "B5_14") (pintype "bidirectional"))
    )
    (net (code "58") (name "Net-(IC24A-PA5)") (class "Default")
      (node (ref "IC24") (pin "7") (pinfunction "PA5_7") (pintype "bidirectional"))
      (node (ref "IC25") (pin "13") (pinfunction "B6_13") (pintype "bidirectional"))
    )
    (net (code "59") (name "Net-(IC24A-PA6)") (class "Default")
      (node (ref "IC24") (pin "8") (pinfunction "PA6_8") (pintype "bidirectional"))
      (node (ref "IC25") (pin "12") (pinfunction "B7_12") (pintype "bidirectional"))
    )
    (net (code "60") (name "Net-(IC24A-PA7)") (class "Default")
      (node (ref "IC24") (pin "9") (pinfunction "PA7_9") (pintype "bidirectional"))
      (node (ref "IC25") (pin "11") (pinfunction "B8_11") (pintype "bidirectional"))
    )
    (net (code "61") (name "Net-(IC24A-PB0)") (class "Default")
      (node (ref "IC24") (pin "10") (pinfunction "PB0_10") (pintype "bidirectional"))
      (node (ref "IC26") (pin "18") (pinfunction "B1_18") (pintype "bidirectional"))
    )
    (net (code "62") (name "Net-(IC24A-PB1)") (class "Default")
      (node (ref "IC24") (pin "11") (pinfunction "PB1_11") (pintype "bidirectional"))
      (node (ref "IC26") (pin "17") (pinfunction "B2_17") (pintype "bidirectional"))
    )
    (net (code "63") (name "Net-(IC24A-PB2)") (class "Default")
      (node (ref "IC24") (pin "12") (pinfunction "PB2_12") (pintype "bidirectional"))
      (node (ref "IC26") (pin "16") (pinfunction "B3_16") (pintype "bidirectional"))
    )
    (net (code "64") (name "Net-(IC24A-PB3)") (class "Default")
      (node (ref "IC24") (pin "13") (pinfunction "PB3_13") (pintype "bidirectional"))
      (node (ref "IC26") (pin "15") (pinfunction "B4_15") (pintype "bidirectional"))
    )
    (net (code "65") (name "Net-(IC24A-PB4)") (class "Default")
      (node (ref "IC24") (pin "14") (pinfunction "PB4_14") (pintype "bidirectional"))
      (node (ref "IC26") (pin "14") (pinfunction "B5_14") (pintype "bidirectional"))
    )
    (net (code "66") (name "Net-(IC24A-PB5)") (class "Default")
      (node (ref "IC24") (pin "15") (pinfunction "PB5_15") (pintype "bidirectional"))
      (node (ref "IC26") (pin "13") (pinfunction "B6_13") (pintype "bidirectional"))
    )
    (net (code "67") (name "Net-(IC24A-PB6)") (class "Default")
      (node (ref "IC24") (pin "16") (pinfunction "PB6_16") (pintype "bidirectional"))
      (node (ref "IC26") (pin "12") (pinfunction "B7_12") (pintype "bidirectional"))
    )
    (net (code "68") (name "Net-(IC24A-PB7)") (class "Default")
      (node (ref "IC24") (pin "17") (pinfunction "PB7_17") (pintype "bidirectional"))
      (node (ref "IC26") (pin "11") (pinfunction "B8_11") (pintype "bidirectional"))
    )
    (net (code "69") (name "Net-(IC27A-CV)") (class "Default")
      (node (ref "C7") (pin "1") (pinfunction "1_1") (pintype "passive"))
      (node (ref "IC27") (pin "3") (pinfunction "CV_3") (pintype "input"))
    )
    (net (code "70") (name "Net-(IC27A-DIS)") (class "Default")
      (node (ref "IC27") (pin "1") (pinfunction "DIS_1") (pintype "input"))
      (node (ref "R10") (pin "2") (pinfunction "2_2") (pintype "passive"))
      (node (ref "R9") (pin "1") (pinfunction "1_1") (pintype "passive"))
    )
    (net (code "71") (name "Net-(IC27A-THR)") (class "Default")
      (node (ref "C") (pin "1") (pinfunction "1_1") (pintype "passive"))
      (node (ref "C6") (pin "1") (pinfunction "1_1") (pintype "passive"))
      (node (ref "IC27") (pin "2") (pinfunction "THR_2") (pintype "input"))
      (node (ref "IC27") (pin "6") (pinfunction "TR_6") (pintype "input"))
      (node (ref "R11") (pin "A") (pinfunction "A_A") (pintype "passive"))
      (node (ref "R11") (pin "S") (pinfunction "S_S") (pintype "passive"))
    )
    (net (code "72") (name "Net-(IC27B-CV)") (class "Default")
      (node (ref "C5") (pin "1") (pinfunction "1_1") (pintype "passive"))
      (node (ref "IC27") (pin "11") (pinfunction "CV_11") (pintype "input"))
    )
    (net (code "73") (name "Net-(IC27B-DIS)") (class "Default")
      (node (ref "IC27") (pin "13") (pinfunction "DIS_13") (pintype "input"))
      (node (ref "R3") (pin "1") (pinfunction "1_1") (pintype "passive"))
      (node (ref "R4") (pin "2") (pinfunction "2_2") (pintype "passive"))
    )
    (net (code "74") (name "Net-(IC27B-THR)") (class "Default")
      (node (ref "C4") (pin "1") (pinfunction "1_1") (pintype "passive"))
      (node (ref "IC27") (pin "12") (pinfunction "THR_12") (pintype "input"))
      (node (ref "IC27") (pin "8") (pinfunction "TR_8") (pintype "input"))
      (node (ref "R4") (pin "1") (pinfunction "1_1") (pintype "passive"))
    )
    (net (code "75") (name "Net-(LED1-PadA)") (class "Default")
      (node (ref "LED1") (pin "A") (pinfunction "A_A") (pintype "passive"))
      (node (ref "R12") (pin "1") (pinfunction "1_1") (pintype "passive"))
    )
    (net (code "76") (name "Net-(R10-Pad1)") (class "Default")
      (node (ref "R10") (pin "1") (pinfunction "1_1") (pintype "passive"))
      (node (ref "R11") (pin "E") (pinfunction "E_E") (pintype "passive"))
    )
    (net (code "77") (name "P1") (class "Default")
      (node (ref "EPROM") (pin "2") (pinfunction "2_2") (pintype "passive"))
      (node (ref "IC29") (pin "1") (pinfunction "VPP_1") (pintype "input"))
    )
    (net (code "78") (name "P27") (class "Default")
      (node (ref "EPROM") (pin "4") (pinfunction "4_4") (pintype "passive"))
      (node (ref "IC29") (pin "27") (pinfunction "A14_27") (pintype "input"))
    )
    (net (code "79") (name "PIA-A0") (class "Default")
      (node (ref "CORE-IO") (pin "1") (pinfunction "1_1") (pintype "passive"))
      (node (ref "IC25") (pin "2") (pinfunction "A1_2") (pintype "bidirectional"))
    )
    (net (code "80") (name "PIA-A1") (class "Default")
      (node (ref "CORE-IO") (pin "2") (pinfunction "2_2") (pintype "passive"))
      (node (ref "IC25") (pin "3") (pinfunction "A2_3") (pintype "bidirectional"))
    )
    (net (code "81") (name "PIA-A2") (class "Default")
      (node (ref "CORE-IO") (pin "3") (pinfunction "3_3") (pintype "passive"))
      (node (ref "IC25") (pin "4") (pinfunction "A3_4") (pintype "bidirectional"))
    )
    (net (code "82") (name "PIA-A3") (class "Default")
      (node (ref "CORE-IO") (pin "4") (pinfunction "4_4") (pintype "passive"))
      (node (ref "IC25") (pin "5") (pinfunction "A4_5") (pintype "bidirectional"))
    )
    (net (code "83") (name "PIA-A4") (class "Default")
      (node (ref "CORE-IO") (pin "5") (pinfunction "5_5") (pintype "passive"))
      (node (ref "IC25") (pin "6") (pinfunction "A5_6") (pintype "bidirectional"))
    )
    (net (code "84") (name "PIA-A5") (class "Default")
      (node (ref "CORE-IO") (pin "6") (pinfunction "6_6") (pintype "passive"))
      (node (ref "IC25") (pin "7") (pinfunction "A6_7") (pintype "bidirectional"))
    )
    (net (code "85") (name "PIA-A6") (class "Default")
      (node (ref "CORE-IO") (pin "7") (pinfunction "7_7") (pintype "passive"))
      (node (ref "IC25") (pin "8") (pinfunction "A7_8") (pintype "bidirectional"))
    )
    (net (code "86") (name "PIA-A7") (class "Default")
      (node (ref "CORE-IO") (pin "8") (pinfunction "8_8") (pintype "passive"))
      (node (ref "IC25") (pin "9") (pinfunction "A8_9") (pintype "bidirectional"))
    )
    (net (code "87") (name "PIA-B0") (class "Default")
      (node (ref "CORE-IO") (pin "13") (pinfunction "13_13") (pintype "passive"))
      (node (ref "IC26") (pin "2") (pinfunction "A1_2") (pintype "bidirectional"))
    )
    (net (code "88") (name "PIA-B1") (class "Default")
      (node (ref "CORE-IO") (pin "14") (pinfunction "14_14") (pintype "passive"))
      (node (ref "IC26") (pin "3") (pinfunction "A2_3") (pintype "bidirectional"))
    )
    (net (code "89") (name "PIA-B2") (class "Default")
      (node (ref "CORE-IO") (pin "15") (pinfunction "15_15") (pintype "passive"))
      (node (ref "IC26") (pin "4") (pinfunction "A3_4") (pintype "bidirectional"))
    )
    (net (code "90") (name "PIA-B3") (class "Default")
      (node (ref "CORE-IO") (pin "16") (pinfunction "16_16") (pintype "passive"))
      (node (ref "IC26") (pin "5") (pinfunction "A4_5") (pintype "bidirectional"))
    )
    (net (code "91") (name "PIA-B4") (class "Default")
      (node (ref "CORE-IO") (pin "17") (pinfunction "17_17") (pintype "passive"))
      (node (ref "IC26") (pin "6") (pinfunction "A5_6") (pintype "bidirectional"))
    )
    (net (code "92") (name "PIA-B5") (class "Default")
      (node (ref "CORE-IO") (pin "18") (pinfunction "18_18") (pintype "passive"))
      (node (ref "IC26") (pin "7") (pinfunction "A6_7") (pintype "bidirectional"))
    )
    (net (code "93") (name "PIA-B6") (class "Default")
      (node (ref "CORE-IO") (pin "19") (pinfunction "19_19") (pintype "passive"))
      (node (ref "IC26") (pin "8") (pinfunction "A7_8") (pintype "bidirectional"))
    )
    (net (code "94") (name "PIA-B7") (class "Default")
      (node (ref "CORE-IO") (pin "20") (pinfunction "20_20") (pintype "passive"))
      (node (ref "IC26") (pin "9") (pinfunction "A8_9") (pintype "bidirectional"))
    )
    (net (code "95") (name "Q") (class "Default")
      (node (ref "IC17") (pin "35") (pinfunction "Q_35") (pintype "input"))
      (node (ref "IC2") (pin "12") (pinfunction "Q_12") (pintype "output"))
      (node (ref "IC2") (pin "7") (pinfunction "J_7") (pintype "input"))
    )
    (net (code "96") (name "RX") (class "Default")
      (node (ref "IC20") (pin "12") (pinfunction "R1OUT_12") (pintype "output"))
      (node (ref "IC21") (pin "2") (pinfunction "RXDATA_2") (pintype "input"))
    )
    (net (code "97") (name "RXD") (class "Default")
      (node (ref "COM") (pin "3") (pinfunction "3_3") (pintype "passive"))
      (node (ref "IC20") (pin "13") (pinfunction "R1IN_13") (pintype "input"))
      (node (ref "RS-232") (pin "3") (pinfunction "3_3") (pintype "passive"))
    )
    (net (code "98") (name "R{slash}~{W}") (class "Default")
      (node (ref "EPROM") (pin "5") (pinfunction "5_5") (pintype "passive"))
      (node (ref "IC17") (pin "32") (pinfunction "R/~{W}_32") (pintype "output"))
      (node (ref "IC21") (pin "13") (pinfunction "R/~{W}_13") (pintype "input"))
      (node (ref "IC22") (pin "27") (pinfunction "~{WE}_27") (pintype "input"))
      (node (ref "IC24") (pin "21") (pinfunction "R/~{W}_21") (pintype "input"))
    )
    (net (code "99") (name "TX") (class "Default")
      (node (ref "IC20") (pin "11") (pinfunction "T1IN_11") (pintype "input"))
      (node (ref "IC21") (pin "6") (pinfunction "TXDATA_6") (pintype "output"))
    )
    (net (code "100") (name "TXD") (class "Default")
      (node (ref "COM") (pin "2") (pinfunction "2_2") (pintype "passive"))
      (node (ref "IC20") (pin "14") (pinfunction "T1OUT_14") (pintype "output"))
      (node (ref "RS-232") (pin "1") (pinfunction "1_1") (pintype "passive"))
    )
    (net (code "101") (name "VCC") (class "Default")
      (node (ref "BYP17") (pin "1") (pinfunction "1_1") (pintype "passive"))
      (node (ref "BYP18") (pin "1") (pinfunction "1_1") (pintype "passive"))
      (node (ref "BYP19") (pin "1") (pinfunction "1_1") (pintype "passive"))
      (node (ref "BYP2") (pin "1") (pinfunction "1_1") (pintype "passive"))
      (node (ref "BYP20") (pin "1") (pinfunction "1_1") (pintype "passive"))
      (node (ref "BYP21") (pin "1") (pinfunction "1_1") (pintype "passive"))
      (node (ref "BYP22") (pin "1") (pinfunction "1_1") (pintype "passive"))
      (node (ref "BYP23") (pin "1") (pinfunction "1_1") (pintype "passive"))
      (node (ref "BYP24") (pin "1") (pinfunction "1_1") (pintype "passive"))
      (node (ref "BYP25") (pin "1") (pinfunction "1_1") (pintype "passive"))
      (node (ref "BYP26") (pin "1") (pinfunction "1_1") (pintype "passive"))
      (node (ref "BYP27") (pin "1") (pinfunction "1_1") (pintype "passive"))
      (node (ref "BYP28") (pin "1") (pinfunction "1_1") (pintype "passive"))
      (node (ref "BYP29") (pin "1") (pinfunction "1_1") (pintype "passive"))
      (node (ref "C10") (pin "1") (pinfunction "1_1") (pintype "passive"))
      (node (ref "CORE-IO") (pin "12") (pinfunction "12_12") (pintype "passive"))
      (node (ref "CORE-IO") (pin "9") (pinfunction "9_9") (pintype "passive"))
      (node (ref "DEBUG") (pin "2") (pinfunction "2_2") (pintype "passive"))
      (node (ref "EP-1") (pin "3") (pinfunction "3_3") (pintype "passive"))
      (node (ref "EPROM") (pin "1") (pinfunction "1_1") (pintype "passive"))
      (node (ref "IC17") (pin "7") (pinfunction "VCC_7") (pintype "power_in"))
      (node (ref "IC2") (pin "2") (pinfunction "CL_2") (pintype "input"))
      (node (ref "IC2") (pin "6") (pinfunction "CL_6") (pintype "input"))
      (node (ref "IC21") (pin "10") (pinfunction "CS1_10") (pintype "input"))
      (node (ref "IC21") (pin "12") (pinfunction "VCC_12") (pintype "power_in"))
      (node (ref "IC21") (pin "8") (pinfunction "CS0_8") (pintype "input"))
      (node (ref "IC22") (pin "28") (pinfunction "VCC_28") (pintype "power_in"))
      (node (ref "IC23") (pin "1") (pinfunction "VPP_1") (pintype "input"))
      (node (ref "IC23") (pin "28") (pinfunction "VCC_28") (pintype "power_in"))
      (node (ref "IC24") (pin "20") (pinfunction "VCC_20") (pintype "power_in"))
      (node (ref "IC24") (pin "22") (pinfunction "CS0_22") (pintype "input"))
      (node (ref "IC24") (pin "24") (pinfunction "CS1_24") (pintype "input"))
      (node (ref "IC27") (pin "10") (pinfunction "R_10") (pintype "input"))
      (node (ref "IC27") (pin "14") (pinfunction "V+_14") (pintype "power_in"))
      (node (ref "IC27") (pin "4") (pinfunction "R_4") (pintype "input"))
      (node (ref "JP4") (pin "2") (pinfunction "2_2") (pintype "passive"))
      (node (ref "QG1") (pin "14") (pinfunction "VCC_14") (pintype "power_in"))
      (node (ref "R1") (pin "2") (pinfunction "2_2") (pintype "passive"))
      (node (ref "R12") (pin "2") (pinfunction "2_2") (pintype "passive"))
      (node (ref "R14") (pin "2") (pinfunction "2_2") (pintype "passive"))
      (node (ref "R2") (pin "2") (pinfunction "2_2") (pintype "passive"))
      (node (ref "R3") (pin "2") (pinfunction "2_2") (pintype "passive"))
      (node (ref "R5") (pin "2") (pinfunction "2_2") (pintype "passive"))
      (node (ref "R6") (pin "2") (pinfunction "2_2") (pintype "passive"))
      (node (ref "R7") (pin "2") (pinfunction "2_2") (pintype "passive"))
      (node (ref "R8") (pin "2") (pinfunction "2_2") (pintype "passive"))
      (node (ref "R9") (pin "2") (pinfunction "2_2") (pintype "passive"))
    )
    (net (code "102") (name "unconnected-(COM-Pad1)") (class "Default")
      (node (ref "COM") (pin "1") (pinfunction "1_1") (pintype "passive"))
    )
    (net (code "103") (name "unconnected-(COM-Pad9)") (class "Default")
      (node (ref "COM") (pin "9") (pinfunction "9_9") (pintype "passive"))
    )
    (net (code "104") (name "unconnected-(IC17A-AVMA-Pad36)") (class "Default")
      (node (ref "IC17") (pin "36") (pinfunction "AVMA_36") (pintype "output"))
    )
    (net (code "105") (name "unconnected-(IC17A-BA-Pad6)") (class "Default")
      (node (ref "IC17") (pin "6") (pinfunction "BA_6") (pintype "output"))
    )
    (net (code "106") (name "unconnected-(IC17A-BS-Pad5)") (class "Default")
      (node (ref "IC17") (pin "5") (pinfunction "BS_5") (pintype "output"))
    )
    (net (code "107") (name "unconnected-(IC17A-BUSY-Pad33)") (class "Default")
      (node (ref "IC17") (pin "33") (pinfunction "BUSY_33") (pintype "output"))
    )
    (net (code "108") (name "unconnected-(IC17A-LIC-Pad38)") (class "Default")
      (node (ref "IC17") (pin "38") (pinfunction "LIC_38") (pintype "output"))
    )
    (net (code "109") (name "unconnected-(IC19A-Y0-Pad15)") (class "Default")
      (node (ref "IC19") (pin "15") (pinfunction "Y0_15") (pintype "output"))
    )
    (net (code "110") (name "unconnected-(IC19A-Y1-Pad14)") (class "Default")
      (node (ref "IC19") (pin "14") (pinfunction "Y1_14") (pintype "output"))
    )
    (net (code "111") (name "unconnected-(IC19A-Y2-Pad13)") (class "Default")
      (node (ref "IC19") (pin "13") (pinfunction "Y2_13") (pintype "output"))
    )
    (net (code "112") (name "unconnected-(IC19A-Y3-Pad12)") (class "Default")
      (node (ref "IC19") (pin "12") (pinfunction "Y3_12") (pintype "output"))
    )
    (net (code "113") (name "unconnected-(IC19A-Y4-Pad11)") (class "Default")
      (node (ref "IC19") (pin "11") (pinfunction "Y4_11") (pintype "output"))
    )
    (net (code "114") (name "unconnected-(IC19A-Y5-Pad10)") (class "Default")
      (node (ref "IC19") (pin "10") (pinfunction "Y5_10") (pintype "output"))
    )
    (net (code "115") (name "unconnected-(IC20A-R2OUT-Pad9)") (class "Default")
      (node (ref "IC20") (pin "9") (pinfunction "R2OUT_9") (pintype "output"))
    )
    (net (code "116") (name "unconnected-(IC22-NC-Pad1)") (class "Default")
      (node (ref "IC22") (pin "1") (pinfunction "NC_1") (pintype "no_connect"))
    )
    (net (code "117") (name "unconnected-(IC28A-Y1-Pad5)") (class "Default")
      (node (ref "IC28") (pin "5") (pinfunction "Y1_5") (pintype "output"))
    )
    (net (code "118") (name "unconnected-(IC28A-Y2-Pad6)") (class "Default")
      (node (ref "IC28") (pin "6") (pinfunction "Y2_6") (pintype "output"))
    )
    (net (code "119") (name "unconnected-(IC28B-Y0-Pad12)") (class "Default")
      (node (ref "IC28") (pin "12") (pinfunction "Y0_12") (pintype "output"))
    )
    (net (code "120") (name "~{4-B}") (class "Default")
      (node (ref "IC28") (pin "9") (pinfunction "Y3_9") (pintype "output"))
      (node (ref "IC29") (pin "20") (pinfunction "~{CE}_20") (pintype "input"))
      (node (ref "IC29") (pin "22") (pinfunction "~{OE}_22") (pintype "input"))
    )
    (net (code "121") (name "~{0123}") (class "Default")
      (node (ref "IC19") (pin "5") (pinfunction "G2B_5") (pintype "input"))
      (node (ref "IC22") (pin "20") (pinfunction "~{CS1}_20") (pintype "input"))
      (node (ref "IC22") (pin "22") (pinfunction "~{OE}_22") (pintype "input"))
      (node (ref "IC28") (pin "11") (pinfunction "Y1_11") (pintype "output"))
    )
    (net (code "122") (name "~{CDEF}") (class "Default")
      (node (ref "IC23") (pin "20") (pinfunction "~{CE}_20") (pintype "input"))
      (node (ref "IC23") (pin "22") (pinfunction "~{OE}_22") (pintype "input"))
      (node (ref "IC28") (pin "10") (pinfunction "Y2_10") (pintype "output"))
    )
    (net (code "123") (name "~{EP1}") (class "Default")
      (node (ref "IC28") (pin "14") (pinfunction "A_14") (pintype "input"))
      (node (ref "IC28") (pin "7") (pinfunction "Y3_7") (pintype "output"))
    )
    (net (code "124") (name "~{FIRQ}") (class "Default")
      (node (ref "IC17") (pin "4") (pinfunction "FIRQ_4") (pintype "input"))
      (node (ref "IC24") (pin "37") (pinfunction "IRQB_37") (pintype "open_collector"))
      (node (ref "IC24") (pin "38") (pinfunction "IRQA_38") (pintype "open_collector"))
      (node (ref "R8") (pin "1") (pinfunction "1_1") (pintype "passive"))
    )
    (net (code "125") (name "~{HLT}") (class "Default")
      (node (ref "IC17") (pin "40") (pinfunction "HALT_40") (pintype "input"))
      (node (ref "R5") (pin "1") (pinfunction "1_1") (pintype "passive"))
    )
    (net (code "126") (name "~{IO-E}") (class "Default")
      (node (ref "IC19") (pin "9") (pinfunction "Y6_9") (pintype "output"))
      (node (ref "IC24") (pin "23") (pinfunction "CS2_23") (pintype "input"))
    )
    (net (code "127") (name "~{IO-F}") (class "Default")
      (node (ref "IC19") (pin "7") (pinfunction "Y7_7") (pintype "output"))
      (node (ref "IC21") (pin "9") (pinfunction "CS2_9") (pintype "input"))
    )
    (net (code "128") (name "~{IRQ}") (class "Default")
      (node (ref "IC17") (pin "3") (pinfunction "IRQ_3") (pintype "input"))
      (node (ref "IC21") (pin "7") (pinfunction "IRQ_7") (pintype "output"))
      (node (ref "R7") (pin "1") (pinfunction "1_1") (pintype "passive"))
    )
    (net (code "129") (name "~{NMI}") (class "Default")
      (node (ref "IC17") (pin "2") (pinfunction "NMI_2") (pintype "input"))
      (node (ref "R6") (pin "1") (pinfunction "1_1") (pintype "passive"))
    )
    (net (code "130") (name "~{RST}") (class "Default")
      (node (ref "IC17") (pin "37") (pinfunction "RESET_37") (pintype "input"))
      (node (ref "IC18") (pin "6") (pinfunction "O_6") (pintype "output"))
      (node (ref "IC24") (pin "34") (pinfunction "RESET_34") (pintype "input"))
    )
  )
)
